# MSP430_REV1_5_21_19_NEW1.net
KiCad netlist of a schematic drawn in EAGLE
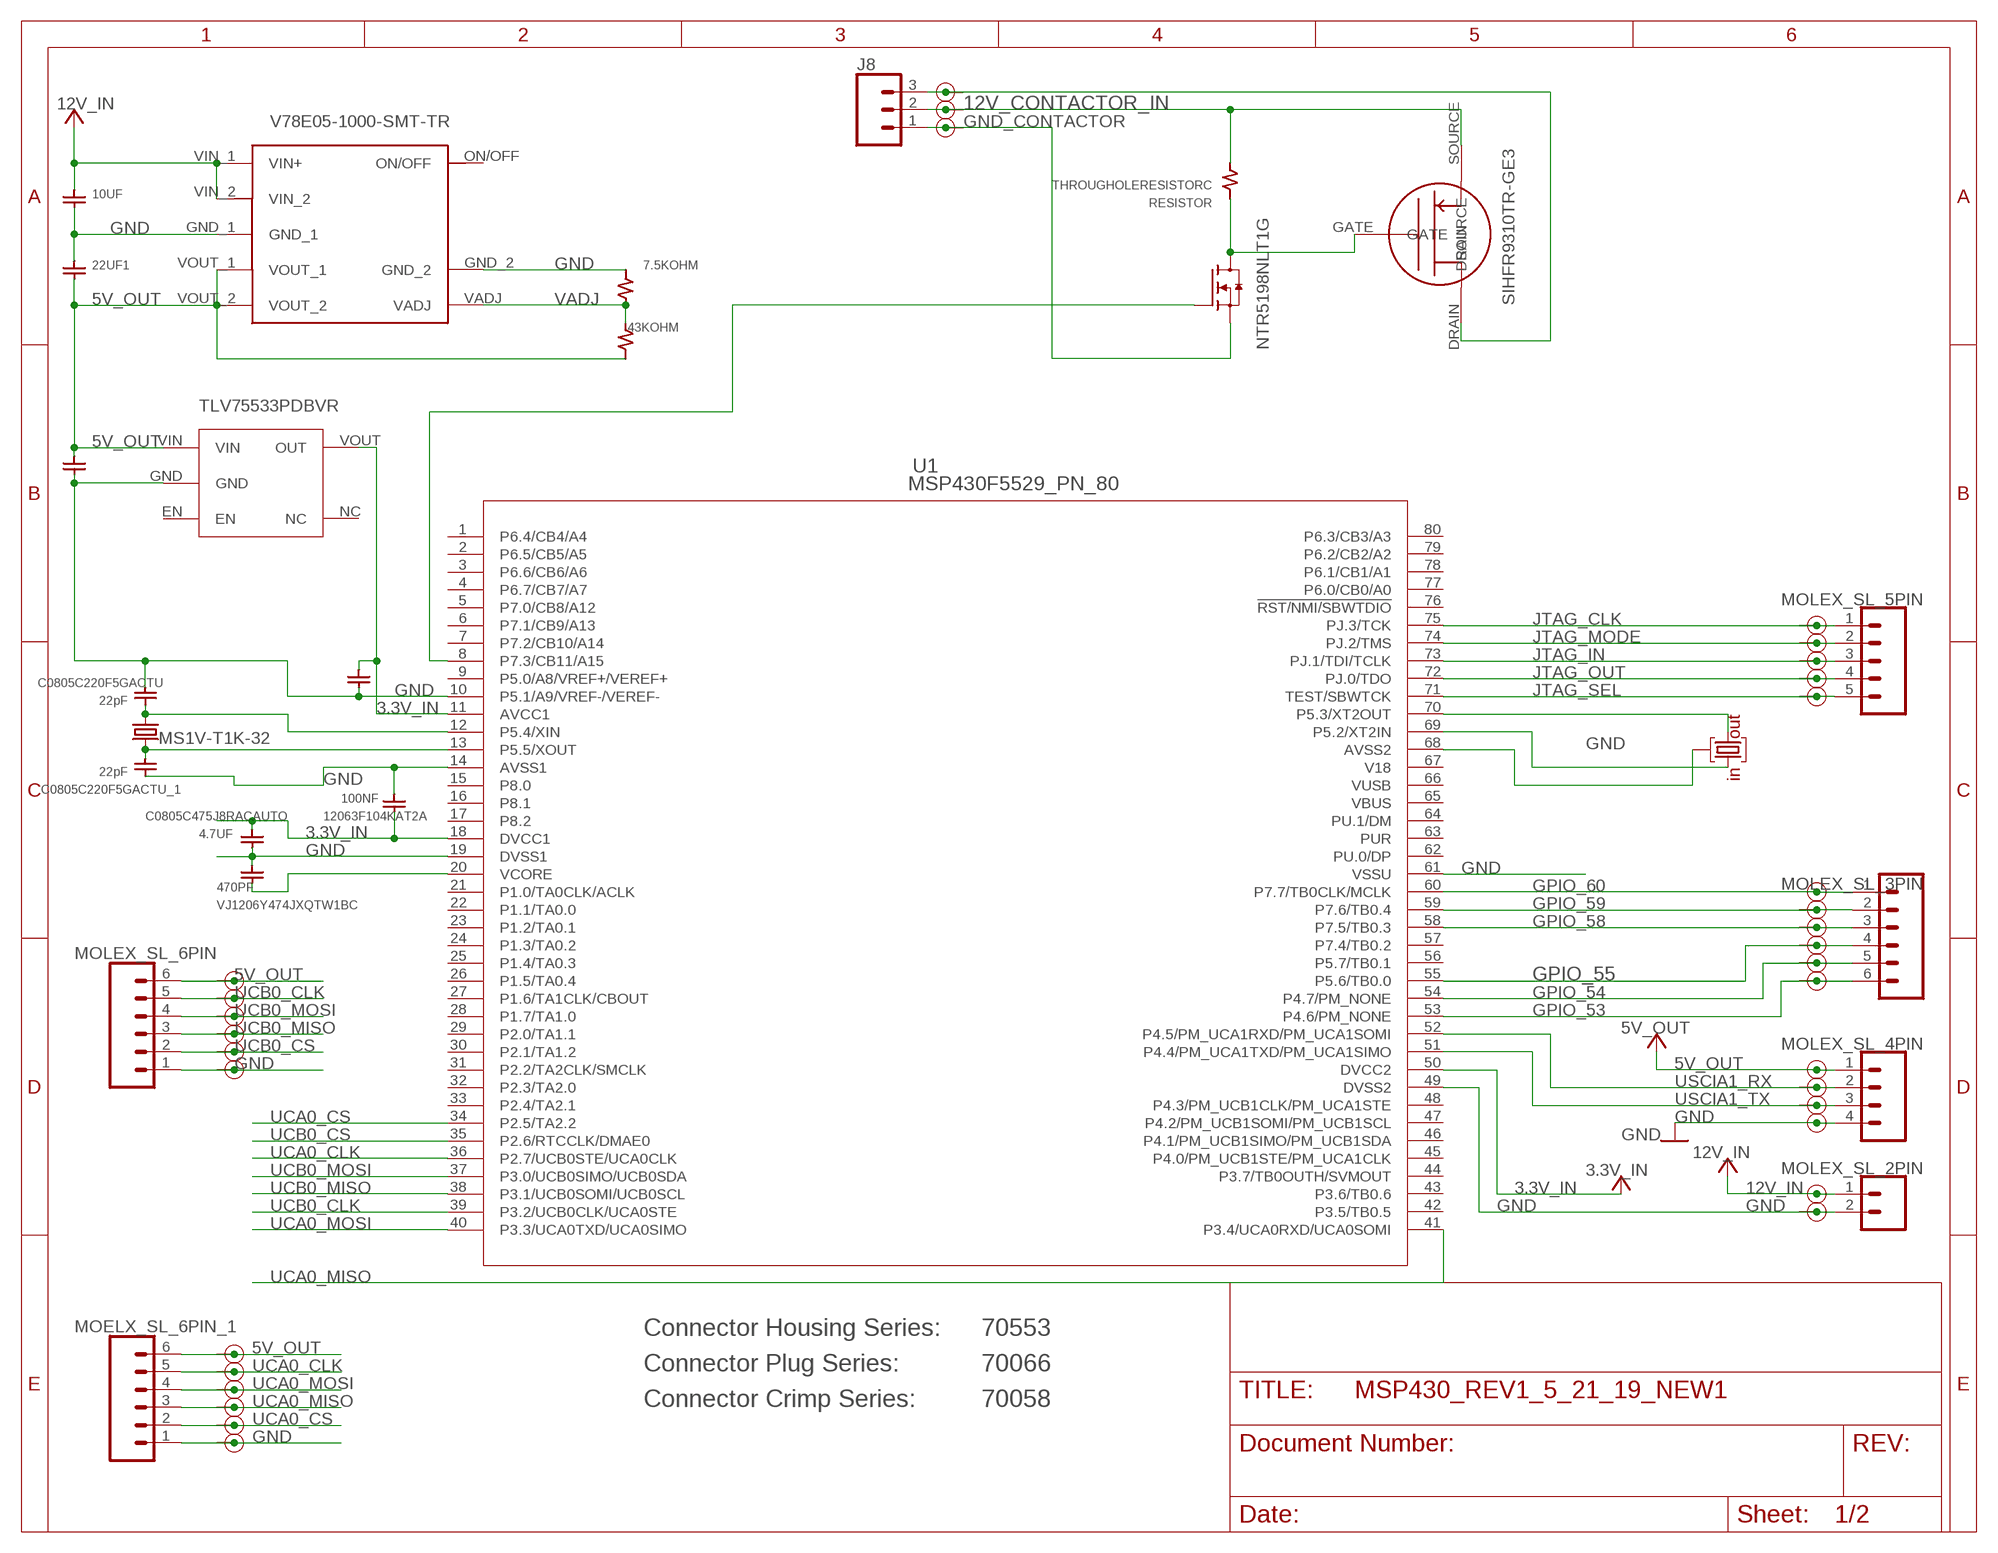
[diagram p0: schematic, sheet 1]
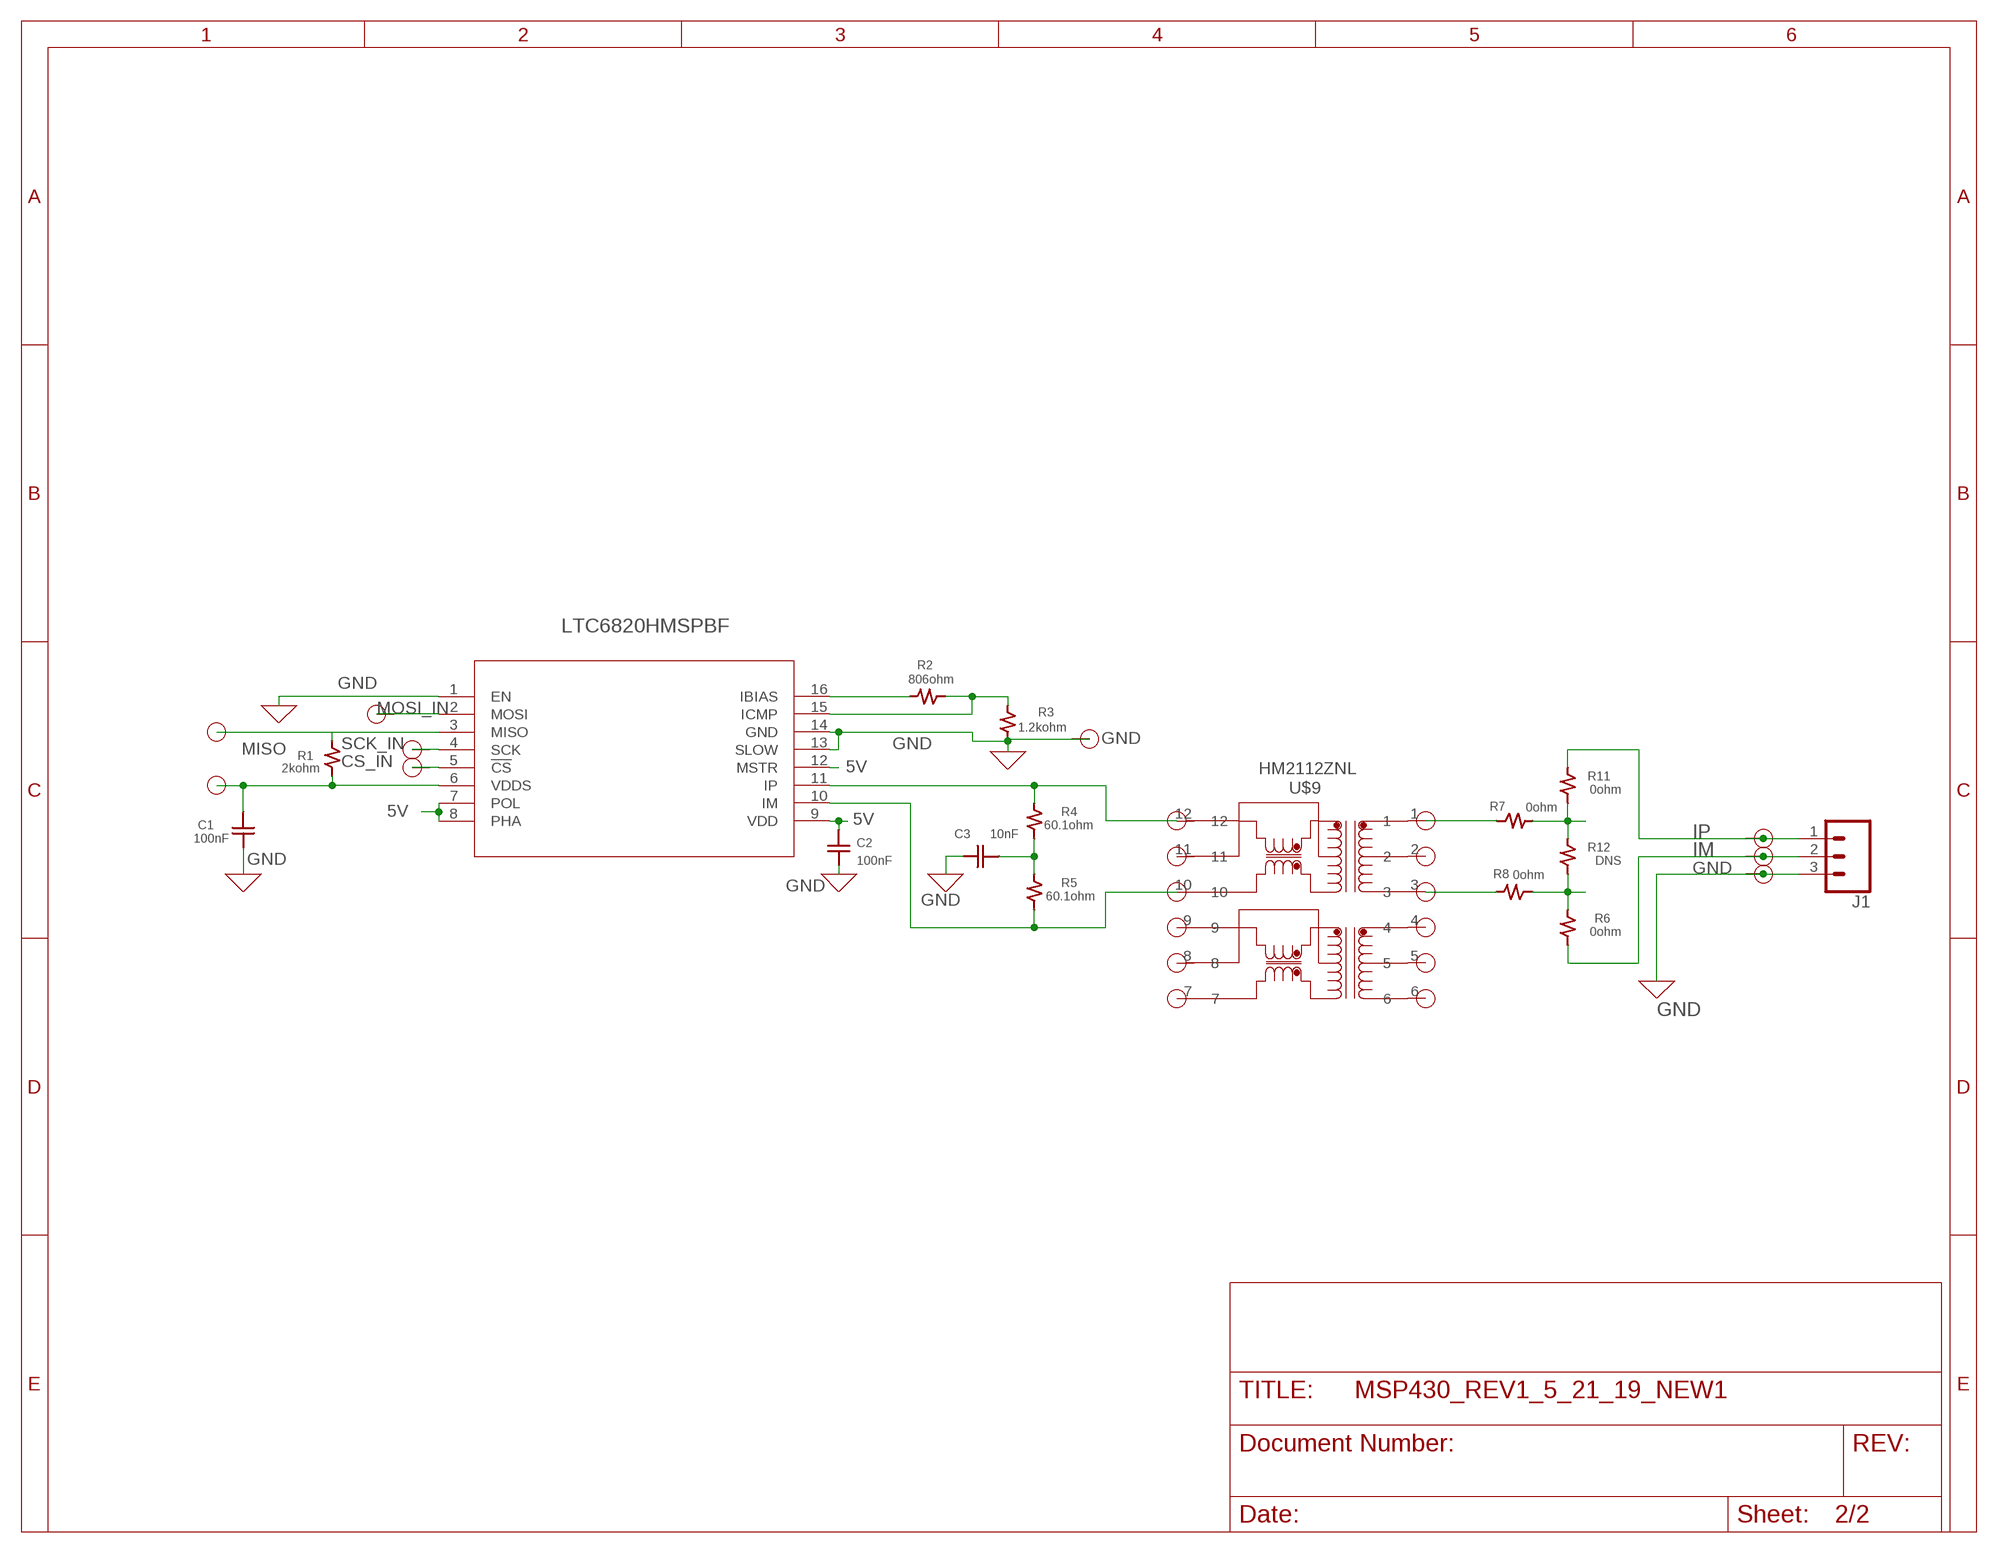
[diagram p1: schematic, sheet 2]

(export (version "E")
  (design (tool "Eeschema 10.0.6"))
  (components
    (comp (ref "C1")
      (value "100nF")
      (footprint "eagle-import:0805_CAPACITOR")
      (fields (field (name "MPN") "MC0805B104K160CT"))
      (libsource (lib "eagle-import") (part "0805_CAPACITOR"))
    )
    (comp (ref "C2")
      (value "100nF")
      (footprint "eagle-import:0805_CAPACITOR")
      (fields (field (name "MPN") "MC0805B104K160CT"))
      (libsource (lib "eagle-import") (part "0805_CAPACITOR"))
    )
    (comp (ref "C3")
      (value "10nF")
      (footprint "eagle-import:0805_CAPACITOR")
      (fields (field (name "MPN") "MC0805B104K160CT"))
      (libsource (lib "eagle-import") (part "0805_CAPACITOR"))
    )
    (comp (ref "CS")
      (value "HEADER_PIN_2.15/1.0")
      (footprint "eagle-import:2,15_1,0")
      (libsource (lib "eagle-import") (part "HEADER_PIN_2.15/1.0"))
    )
    (comp (ref "GND")
      (value "HEADER_PIN_2.15/1.0")
      (footprint "eagle-import:2,15_1,0")
      (libsource (lib "eagle-import") (part "HEADER_PIN_2.15/1.0"))
    )
    (comp (ref "J1")
      (value "CONN_03")
      (footprint "eagle-import:1X03")
      (libsource (lib "eagle-import") (part "CONN_03"))
    )
    (comp (ref "MISO")
      (value "HEADER_PIN_2.15/1.0")
      (footprint "eagle-import:2,15_1,0")
      (libsource (lib "eagle-import") (part "HEADER_PIN_2.15/1.0"))
    )
    (comp (ref "MOSI")
      (value "HEADER_PIN_2.15/1.0")
      (footprint "eagle-import:2,15_1,0")
      (libsource (lib "eagle-import") (part "HEADER_PIN_2.15/1.0"))
    )
    (comp (ref "R1")
      (value "2kohm")
      (footprint "eagle-import:0805_RESISTOR")
      (fields (field (name "MPN") "ERJ-6ENF2001V"))
      (libsource (lib "eagle-import") (part "0805_RESISTOR"))
    )
    (comp (ref "R2")
      (value "806ohm")
      (footprint "eagle-import:0805_RESISTOR")
      (fields (field (name "MF") "VISHAY/DALE") (field (name "MPN") "CRCW0805806RFKEA"))
      (libsource (lib "eagle-import") (part "0805_RESISTOR"))
    )
    (comp (ref "R3")
      (value "1.2kohm")
      (footprint "eagle-import:0805_RESISTOR")
      (fields (field (name "MPN") "MC0805S8F1201T5E"))
      (libsource (lib "eagle-import") (part "0805_RESISTOR"))
    )
    (comp (ref "R4")
      (value "60.1ohm")
      (footprint "eagle-import:0805_RESISTOR")
      (fields (field (name "MF") "BOURNS, INC.") (field (name "MPN") "CR0805-FX-1200GLF"))
      (libsource (lib "eagle-import") (part "0805_RESISTOR"))
    )
    (comp (ref "R5")
      (value "60.1ohm")
      (footprint "eagle-import:0805_RESISTOR")
      (fields (field (name "MF") "BOURNS, INC.") (field (name "MPN") "CR0805-FX-1200GLF"))
      (libsource (lib "eagle-import") (part "0805_RESISTOR"))
    )
    (comp (ref "R6")
      (value "0ohm")
      (footprint "eagle-import:0805_RESISTOR")
      (fields (field (name "MF") "BOURNS, INC.") (field (name "MPN") "CR0805-FX-1200GLF"))
      (libsource (lib "eagle-import") (part "0805_RESISTOR"))
    )
    (comp (ref "R7")
      (value "0ohm")
      (footprint "eagle-import:0805_RESISTOR")
      (fields (field (name "MF") "BOURNS, INC.") (field (name "MPN") "CR0805-FX-1200GLF"))
      (libsource (lib "eagle-import") (part "0805_RESISTOR"))
    )
    (comp (ref "R8")
      (value "0ohm")
      (footprint "eagle-import:0805_RESISTOR")
      (fields (field (name "MF") "BOURNS, INC.") (field (name "MPN") "CR0805-FX-1200GLF"))
      (libsource (lib "eagle-import") (part "0805_RESISTOR"))
    )
    (comp (ref "R11")
      (value "0ohm")
      (footprint "eagle-import:0805_RESISTOR")
      (fields (field (name "MF") "BOURNS, INC.") (field (name "MPN") "CR0805-FX-1200GLF"))
      (libsource (lib "eagle-import") (part "0805_RESISTOR"))
    )
    (comp (ref "R12")
      (value "DNS")
      (footprint "eagle-import:0805_RESISTOR")
      (fields (field (name "MF") "BOURNS, INC.") (field (name "MPN") "CR0805-FX-1200GLF"))
      (libsource (lib "eagle-import") (part "0805_RESISTOR"))
    )
    (comp (ref "SCK")
      (value "HEADER_PIN_2.15/1.0")
      (footprint "eagle-import:2,15_1,0")
      (libsource (lib "eagle-import") (part "HEADER_PIN_2.15/1.0"))
    )
    (comp (ref "U$9")
      (value "HM2112ZNL")
      (footprint "eagle-import:HM2112ZNL_12SMT")
      (libsource (lib "eagle-import") (part "HM2112ZNL"))
    )
    (comp (ref "U$42")
      (value "HEADER_PIN_2.15/1.0")
      (footprint "eagle-import:2,15_1,0")
      (libsource (lib "eagle-import") (part "HEADER_PIN_2.15/1.0"))
    )
    (comp (ref "U$43")
      (value "HEADER_PIN_2.15/1.0")
      (footprint "eagle-import:2,15_1,0")
      (libsource (lib "eagle-import") (part "HEADER_PIN_2.15/1.0"))
    )
    (comp (ref "U$44")
      (value "HEADER_PIN_2.15/1.0")
      (footprint "eagle-import:2,15_1,0")
      (libsource (lib "eagle-import") (part "HEADER_PIN_2.15/1.0"))
    )
    (comp (ref "U2")
      (value "LTC6820HMSPBF")
      (footprint "eagle-import:MSOP-16_MS")
      (fields (field (name "MANUFACTURER_PART_NUMBER") "LTC6820HMS#PBF"))
      (libsource (lib "eagle-import") (part "LTC6820HMSPBF"))
    )
    (comp (ref "VDDS")
      (value "HEADER_PIN_2.15/1.0")
      (footprint "eagle-import:2,15_1,0")
      (libsource (lib "eagle-import") (part "HEADER_PIN_2.15/1.0"))
    )
    (comp (ref "4.7UF")
      (value "C0805C475J8RACAUTO")
      (footprint "eagle-import:C0805C475J8RACAUTO")
      (libsource (lib "eagle-import") (part "C0805C475J8RACAUTO"))
    )
    (comp (ref "7.5KOHM")
      (value "RC2512FK-077K5L")
      (footprint "eagle-import:RC2512FK-077K5L")
      (libsource (lib "eagle-import") (part "RC2512FK-077K5L"))
    )
    (comp (ref "10UF")
      (value "GRT31CR61H106KE01L")
      (footprint "eagle-import:GRT31CR61H106KE01L")
      (libsource (lib "eagle-import") (part "GRT31CR61H106KE01L"))
    )
    (comp (ref "22UF1")
      (value "GRT31CC81C226KE01L")
      (footprint "eagle-import:GRT31CC81C226KE01L")
      (libsource (lib "eagle-import") (part "GRT31CC81C226KE01L"))
    )
    (comp (ref "43KOHM")
      (value "CRCW121043K0FKEAHP")
      (footprint "eagle-import:CRCW121043K0FKEAHP")
      (libsource (lib "eagle-import") (part "CRCW121043K0FKEAHP"))
    )
    (comp (ref "100NF")
      (value "12063F104KAT2A")
      (footprint "eagle-import:12063F104KAT2A")
      (libsource (lib "eagle-import") (part "12063F104KAT2A"))
    )
    (comp (ref "470PF")
      (value "VJ1206Y474JXQTW1BC")
      (footprint "eagle-import:VJ1206Y474JXQTW1BC")
      (libsource (lib "eagle-import") (part "VJ1206Y474JXQTW1BC"))
    )
    (comp (ref "C0805C220F5GACTU")
      (value "22pF")
      (footprint "eagle-import:C0805C220F5GACTU")
      (libsource (lib "eagle-import") (part "C0805C220F5GACTUC0805C220F5GACTU"))
    )
    (comp (ref "C0805C220F5GACTU_1")
      (value "22pF")
      (footprint "eagle-import:C0805C220F5GACTU")
      (libsource (lib "eagle-import") (part "C0805C220F5GACTUC0805C220F5GACTU"))
    )
    (comp (ref "J8")
      (value "CONN_03")
      (footprint "eagle-import:1X03")
      (libsource (lib "eagle-import") (part "CONN_03"))
    )
    (comp (ref "MOELX_SL_6PIN_1")
      (value "CONN_06SILK_FEMALE_PTH")
      (footprint "eagle-import:1X06")
      (libsource (lib "eagle-import") (part "CONN_06SILK_FEMALE_PTH"))
    )
    (comp (ref "MOLEX_SL_2PIN")
      (value "CONN_02")
      (footprint "eagle-import:1X02")
      (libsource (lib "eagle-import") (part "CONN_02"))
    )
    (comp (ref "MOLEX_SL_3PIN")
      (value "CONN_06SILK_FEMALE_PTH")
      (footprint "eagle-import:1X06")
      (libsource (lib "eagle-import") (part "CONN_06SILK_FEMALE_PTH"))
    )
    (comp (ref "MOLEX_SL_4PIN")
      (value "CONN_04")
      (footprint "eagle-import:1X04")
      (libsource (lib "eagle-import") (part "CONN_04"))
    )
    (comp (ref "MOLEX_SL_5PIN")
      (value "CONN_05")
      (footprint "eagle-import:1X05")
      (libsource (lib "eagle-import") (part "CONN_05"))
    )
    (comp (ref "MOLEX_SL_6PIN")
      (value "CONN_06SILK_FEMALE_PTH")
      (footprint "eagle-import:1X06")
      (libsource (lib "eagle-import") (part "CONN_06SILK_FEMALE_PTH"))
    )
    (comp (ref "RESISTOR")
      (value "THROUGHOLERESISTORC")
      (footprint "eagle-import:THROUGHHOLERESISTOR")
      (libsource (lib "eagle-import") (part "THROUGHOLERESISTORCMF6023K000DHR6"))
    )
    (comp (ref "U$1")
      (value "MS1V-T1K-32")
      (footprint "eagle-import:MS1V-T1K")
      (libsource (lib "eagle-import") (part "MS1V-T1K-32"))
    )
    (comp (ref "U$2")
      (value "CSTCR4M00G53U-R0")
      (footprint "eagle-import:CSTCR4M00G53U-R0")
      (libsource (lib "eagle-import") (part "CSTCR4M00G53U-R0"))
    )
    (comp (ref "U$3")
      (value "V78E05-SMT-TR")
      (footprint "eagle-import:V78E05-1000-SMT-TR")
      (libsource (lib "eagle-import") (part "V78E05-SMT-TR"))
    )
    (comp (ref "U$4")
      (value "NTR5198NLT1G")
      (footprint "eagle-import:NTR5198NLT1G")
      (libsource (lib "eagle-import") (part "NTR5198NLT1G"))
    )
    (comp (ref "U$5")
      (value "PMOS")
      (footprint "eagle-import:SIHFR9310TR-GE3")
      (libsource (lib "eagle-import") (part "PMOS"))
    )
    (comp (ref "U$6")
      (value "TLV75533PDBVR")
      (footprint "eagle-import:TLV75533PDBVR")
      (libsource (lib "eagle-import") (part "TLV75533PDBVR"))
    )
    (comp (ref "U$7")
      (value "C0805C105J4RECTU")
      (footprint "eagle-import:C0805C105J4RECTU")
      (libsource (lib "eagle-import") (part "C0805C105J4RECTU"))
    )
    (comp (ref "U$8")
      (value "C0805C105J4RECTU")
      (footprint "eagle-import:C0805C105J4RECTU")
      (libsource (lib "eagle-import") (part "C0805C105J4RECTU"))
    )
    (comp (ref "U$10")
      (value "HEADER_PIN_2.15/1.0")
      (footprint "eagle-import:2,15_1,0")
      (libsource (lib "eagle-import") (part "HEADER_PIN_2.15/1.0"))
    )
    (comp (ref "U$11")
      (value "HEADER_PIN_2.15/1.0")
      (footprint "eagle-import:2,15_1,0")
      (libsource (lib "eagle-import") (part "HEADER_PIN_2.15/1.0"))
    )
    (comp (ref "U$12")
      (value "HEADER_PIN_2.15/1.0")
      (footprint "eagle-import:2,15_1,0")
      (libsource (lib "eagle-import") (part "HEADER_PIN_2.15/1.0"))
    )
    (comp (ref "U$13")
      (value "HEADER_PIN_2.15/1.0")
      (footprint "eagle-import:2,15_1,0")
      (libsource (lib "eagle-import") (part "HEADER_PIN_2.15/1.0"))
    )
    (comp (ref "U$14")
      (value "HEADER_PIN_2.15/1.0")
      (footprint "eagle-import:2,15_1,0")
      (libsource (lib "eagle-import") (part "HEADER_PIN_2.15/1.0"))
    )
    (comp (ref "U$15")
      (value "HEADER_PIN_2.15/1.0")
      (footprint "eagle-import:2,15_1,0")
      (libsource (lib "eagle-import") (part "HEADER_PIN_2.15/1.0"))
    )
    (comp (ref "U$16")
      (value "HEADER_PIN_2.15/1.0")
      (footprint "eagle-import:2,15_1,0")
      (libsource (lib "eagle-import") (part "HEADER_PIN_2.15/1.0"))
    )
    (comp (ref "U$17")
      (value "HEADER_PIN_2.15/1.0")
      (footprint "eagle-import:2,15_1,0")
      (libsource (lib "eagle-import") (part "HEADER_PIN_2.15/1.0"))
    )
    (comp (ref "U$18")
      (value "HEADER_PIN_2.15/1.0")
      (footprint "eagle-import:2,15_1,0")
      (libsource (lib "eagle-import") (part "HEADER_PIN_2.15/1.0"))
    )
    (comp (ref "U$19")
      (value "HEADER_PIN_2.15/1.0")
      (footprint "eagle-import:2,15_1,0")
      (libsource (lib "eagle-import") (part "HEADER_PIN_2.15/1.0"))
    )
    (comp (ref "U$20")
      (value "HEADER_PIN_2.15/1.0")
      (footprint "eagle-import:2,15_1,0")
      (libsource (lib "eagle-import") (part "HEADER_PIN_2.15/1.0"))
    )
    (comp (ref "U$21")
      (value "HEADER_PIN_2.15/1.0")
      (footprint "eagle-import:2,15_1,0")
      (libsource (lib "eagle-import") (part "HEADER_PIN_2.15/1.0"))
    )
    (comp (ref "U$22")
      (value "HEADER_PIN_2.15/1.0")
      (footprint "eagle-import:2,15_1,0")
      (libsource (lib "eagle-import") (part "HEADER_PIN_2.15/1.0"))
    )
    (comp (ref "U$23")
      (value "HEADER_PIN_2.15/1.0")
      (footprint "eagle-import:2,15_1,0")
      (libsource (lib "eagle-import") (part "HEADER_PIN_2.15/1.0"))
    )
    (comp (ref "U$24")
      (value "HEADER_PIN_2.15/1.0")
      (footprint "eagle-import:2,15_1,0")
      (libsource (lib "eagle-import") (part "HEADER_PIN_2.15/1.0"))
    )
    (comp (ref "U$25")
      (value "HEADER_PIN_2.15/1.0")
      (footprint "eagle-import:2,15_1,0")
      (libsource (lib "eagle-import") (part "HEADER_PIN_2.15/1.0"))
    )
    (comp (ref "U$26")
      (value "HEADER_PIN_2.15/1.0")
      (footprint "eagle-import:2,15_1,0")
      (libsource (lib "eagle-import") (part "HEADER_PIN_2.15/1.0"))
    )
    (comp (ref "U$27")
      (value "HEADER_PIN_2.15/1.0")
      (footprint "eagle-import:2,15_1,0")
      (libsource (lib "eagle-import") (part "HEADER_PIN_2.15/1.0"))
    )
    (comp (ref "U$28")
      (value "HEADER_PIN_2.15/1.0")
      (footprint "eagle-import:2,15_1,0")
      (libsource (lib "eagle-import") (part "HEADER_PIN_2.15/1.0"))
    )
    (comp (ref "U$29")
      (value "HEADER_PIN_2.15/1.0")
      (footprint "eagle-import:2,15_1,0")
      (libsource (lib "eagle-import") (part "HEADER_PIN_2.15/1.0"))
    )
    (comp (ref "U$30")
      (value "HEADER_PIN_2.15/1.0")
      (footprint "eagle-import:2,15_1,0")
      (libsource (lib "eagle-import") (part "HEADER_PIN_2.15/1.0"))
    )
    (comp (ref "U$31")
      (value "HEADER_PIN_2.15/1.0")
      (footprint "eagle-import:2,15_1,0")
      (libsource (lib "eagle-import") (part "HEADER_PIN_2.15/1.0"))
    )
    (comp (ref "U$32")
      (value "HEADER_PIN_2.15/1.0")
      (footprint "eagle-import:2,15_1,0")
      (libsource (lib "eagle-import") (part "HEADER_PIN_2.15/1.0"))
    )
    (comp (ref "U$33")
      (value "HEADER_PIN_2.15/1.0")
      (footprint "eagle-import:2,15_1,0")
      (libsource (lib "eagle-import") (part "HEADER_PIN_2.15/1.0"))
    )
    (comp (ref "U$34")
      (value "HEADER_PIN_2.15/1.0")
      (footprint "eagle-import:2,15_1,0")
      (libsource (lib "eagle-import") (part "HEADER_PIN_2.15/1.0"))
    )
    (comp (ref "U$35")
      (value "HEADER_PIN_2.15/1.0")
      (footprint "eagle-import:2,15_1,0")
      (libsource (lib "eagle-import") (part "HEADER_PIN_2.15/1.0"))
    )
    (comp (ref "U$36")
      (value "HEADER_PIN_2.15/1.0")
      (footprint "eagle-import:2,15_1,0")
      (libsource (lib "eagle-import") (part "HEADER_PIN_2.15/1.0"))
    )
    (comp (ref "U$37")
      (value "HEADER_PIN_2.15/1.0")
      (footprint "eagle-import:2,15_1,0")
      (libsource (lib "eagle-import") (part "HEADER_PIN_2.15/1.0"))
    )
    (comp (ref "U$38")
      (value "HEADER_PIN_2.15/1.0")
      (footprint "eagle-import:2,15_1,0")
      (libsource (lib "eagle-import") (part "HEADER_PIN_2.15/1.0"))
    )
    (comp (ref "U$39")
      (value "HEADER_PIN_2.15/1.0")
      (footprint "eagle-import:2,15_1,0")
      (libsource (lib "eagle-import") (part "HEADER_PIN_2.15/1.0"))
    )
    (comp (ref "U$40")
      (value "HEADER_PIN_2.15/1.0")
      (footprint "eagle-import:2,15_1,0")
      (libsource (lib "eagle-import") (part "HEADER_PIN_2.15/1.0"))
    )
    (comp (ref "U$41")
      (value "HEADER_PIN_2.15/1.0")
      (footprint "eagle-import:2,15_1,0")
      (libsource (lib "eagle-import") (part "HEADER_PIN_2.15/1.0"))
    )
    (comp (ref "U1")
      (value "MSP430F5529_PN_80")
      (footprint "eagle-import:PN80")
      (libsource (lib "eagle-import") (part "MSP430F5529_PN_80"))
    )
  )
  (nets
    (net (code "1") (name "3.3V_IN") (class "Default")
      (node (ref "100NF") (pin "1") (pinfunction "P$1_1") (pintype "bidirectional"))
      (node (ref "4.7UF") (pin "2") (pinfunction "P$2_2") (pintype "bidirectional"))
      (node (ref "U$6") (pin "VOUT") (pinfunction "OUT_VOUT") (pintype "bidirectional"))
      (node (ref "U$8") (pin "2") (pinfunction "P$2_2") (pintype "bidirectional"))
      (node (ref "U1") (pin "11") (pinfunction "AVCC1_11") (pintype "power_in"))
      (node (ref "U1") (pin "18") (pinfunction "DVCC1_18") (pintype "power_in"))
      (node (ref "U1") (pin "50") (pinfunction "DVCC2_50") (pintype "power_in"))
    )
    (net (code "2") (name "5V") (class "Default")
      (node (ref "C1") (pin "P$2") (pinfunction "P$2_P$2") (pintype "bidirectional"))
      (node (ref "C2") (pin "P$2") (pinfunction "P$2_P$2") (pintype "bidirectional"))
      (node (ref "R1") (pin "P$2") (pinfunction "P$2_P$2") (pintype "bidirectional"))
      (node (ref "U2") (pin "12") (pinfunction "MSTR_12") (pintype "input"))
      (node (ref "U2") (pin "6") (pinfunction "VDDS_6") (pintype "power_in"))
      (node (ref "U2") (pin "7") (pinfunction "POL_7") (pintype "input"))
      (node (ref "U2") (pin "8") (pinfunction "PHA_8") (pintype "input"))
      (node (ref "U2") (pin "9") (pinfunction "VDD_9") (pintype "power_in"))
      (node (ref "VDDS") (pin "1") (pinfunction "P$1_1") (pintype "bidirectional"))
    )
    (net (code "3") (name "5V_OUT") (class "Default")
      (node (ref "22UF1") (pin "1") (pinfunction "P$1_1") (pintype "bidirectional"))
      (node (ref "43KOHM") (pin "2") (pinfunction "P$2_2") (pintype "bidirectional"))
      (node (ref "MOELX_SL_6PIN_1") (pin "6") (pinfunction "6_6") (pintype "passive"))
      (node (ref "MOLEX_SL_4PIN") (pin "1") (pinfunction "1_1") (pintype "passive"))
      (node (ref "MOLEX_SL_6PIN") (pin "6") (pinfunction "6_6") (pintype "passive"))
      (node (ref "U$11") (pin "1") (pinfunction "P$1_1") (pintype "bidirectional"))
      (node (ref "U$17") (pin "1") (pinfunction "P$1_1") (pintype "bidirectional"))
      (node (ref "U$27") (pin "1") (pinfunction "P$1_1") (pintype "bidirectional"))
      (node (ref "U$3") (pin "VOUT_1") (pinfunction "VOUT_1_VOUT_1") (pintype "output"))
      (node (ref "U$3") (pin "VOUT_2") (pinfunction "VOUT_2_VOUT_2") (pintype "output"))
      (node (ref "U$6") (pin "VIN") (pinfunction "VIN_VIN") (pintype "bidirectional"))
      (node (ref "U$7") (pin "2") (pinfunction "P$2_2") (pintype "bidirectional"))
    )
    (net (code "4") (name "12V_CONTACTOR_IN") (class "Default")
      (node (ref "J8") (pin "2") (pinfunction "2_2") (pintype "passive"))
      (node (ref "RESISTOR") (pin "1") (pinfunction "P$1_1") (pintype "bidirectional"))
      (node (ref "U$40") (pin "1") (pinfunction "P$1_1") (pintype "bidirectional"))
      (node (ref "U$5") (pin "SOURCE") (pinfunction "SOURCE_SOURCE") (pintype "bidirectional"))
    )
    (net (code "5") (name "12V_IN") (class "Default")
      (node (ref "10UF") (pin "2") (pinfunction "P$2_2") (pintype "bidirectional"))
      (node (ref "MOLEX_SL_2PIN") (pin "1") (pinfunction "1_1") (pintype "passive"))
      (node (ref "U$23") (pin "1") (pinfunction "P$1_1") (pintype "bidirectional"))
      (node (ref "U$3") (pin "VIN_1") (pinfunction "VIN+_VIN_1") (pintype "input"))
      (node (ref "U$3") (pin "VIN_2") (pinfunction "VIN_2_VIN_2") (pintype "input"))
    )
    (net (code "6") (name "CS_IN") (class "Default")
      (node (ref "CS") (pin "1") (pinfunction "P$1_1") (pintype "bidirectional"))
      (node (ref "U2") (pin "5") (pinfunction "~{CS}_5") (pintype "bidirectional"))
    )
    (net (code "7") (name "GND") (class "Default")
      (node (ref "100NF") (pin "2") (pinfunction "P$2_2") (pintype "bidirectional"))
      (node (ref "10UF") (pin "1") (pinfunction "P$1_1") (pintype "bidirectional"))
      (node (ref "22UF1") (pin "2") (pinfunction "P$2_2") (pintype "bidirectional"))
      (node (ref "4.7UF") (pin "1") (pinfunction "P$1_1") (pintype "bidirectional"))
      (node (ref "470PF") (pin "2") (pinfunction "P$2_2") (pintype "bidirectional"))
      (node (ref "7.5KOHM") (pin "2") (pinfunction "P$2_2") (pintype "bidirectional"))
      (node (ref "C0805C220F5GACTU") (pin "1") (pinfunction "P$1_1") (pintype "bidirectional"))
      (node (ref "C0805C220F5GACTU_1") (pin "2") (pinfunction "P$2_2") (pintype "bidirectional"))
      (node (ref "C1") (pin "P$1") (pinfunction "P$1_P$1") (pintype "bidirectional"))
      (node (ref "C2") (pin "P$1") (pinfunction "P$1_P$1") (pintype "bidirectional"))
      (node (ref "C3") (pin "P$1") (pinfunction "P$1_P$1") (pintype "bidirectional"))
      (node (ref "GND") (pin "1") (pinfunction "P$1_1") (pintype "bidirectional"))
      (node (ref "J1") (pin "3") (pinfunction "3_3") (pintype "passive"))
      (node (ref "MOELX_SL_6PIN_1") (pin "1") (pinfunction "1_1") (pintype "passive"))
      (node (ref "MOLEX_SL_2PIN") (pin "2") (pinfunction "2_2") (pintype "passive"))
      (node (ref "MOLEX_SL_4PIN") (pin "4") (pinfunction "4_4") (pintype "passive"))
      (node (ref "MOLEX_SL_6PIN") (pin "1") (pinfunction "1_1") (pintype "passive"))
      (node (ref "R3") (pin "P$2") (pinfunction "P$2_P$2") (pintype "bidirectional"))
      (node (ref "U$10") (pin "1") (pinfunction "P$1_1") (pintype "bidirectional"))
      (node (ref "U$16") (pin "1") (pinfunction "P$1_1") (pintype "bidirectional"))
      (node (ref "U$2") (pin "GND") (pinfunction "GND_GND") (pintype "passive"))
      (node (ref "U$22") (pin "1") (pinfunction "P$1_1") (pintype "bidirectional"))
      (node (ref "U$24") (pin "1") (pinfunction "P$1_1") (pintype "bidirectional"))
      (node (ref "U$3") (pin "GND_1") (pinfunction "GND_1_GND_1") (pintype "bidirectional"))
      (node (ref "U$3") (pin "GND_2") (pinfunction "GND_2_GND_2") (pintype "bidirectional"))
      (node (ref "U$44") (pin "1") (pinfunction "P$1_1") (pintype "bidirectional"))
      (node (ref "U$6") (pin "GND") (pinfunction "GND_GND") (pintype "bidirectional"))
      (node (ref "U$7") (pin "1") (pinfunction "P$1_1") (pintype "bidirectional"))
      (node (ref "U$8") (pin "1") (pinfunction "P$1_1") (pintype "bidirectional"))
      (node (ref "U1") (pin "10") (pinfunction "P5.1/A9/VREF-/VEREF-_10") (pintype "bidirectional"))
      (node (ref "U1") (pin "14") (pinfunction "AVSS1_14") (pintype "power_in"))
      (node (ref "U1") (pin "19") (pinfunction "DVSS1_19") (pintype "power_in"))
      (node (ref "U1") (pin "49") (pinfunction "DVSS2_49") (pintype "power_in"))
      (node (ref "U1") (pin "61") (pinfunction "VSSU_61") (pintype "power_in"))
      (node (ref "U1") (pin "68") (pinfunction "AVSS2_68") (pintype "power_in"))
      (node (ref "U2") (pin "1") (pinfunction "EN_1") (pintype "input"))
      (node (ref "U2") (pin "13") (pinfunction "SLOW_13") (pintype "input"))
      (node (ref "U2") (pin "14") (pinfunction "GND_14") (pintype "power_in"))
    )
    (net (code "8") (name "GND_CONTACTOR") (class "Default")
      (node (ref "J8") (pin "1") (pinfunction "1_1") (pintype "passive"))
      (node (ref "U$4") (pin "SOURCE") (pinfunction "SOURCE_SOURCE") (pintype "passive"))
      (node (ref "U$41") (pin "1") (pinfunction "P$1_1") (pintype "bidirectional"))
    )
    (net (code "9") (name "GPIO_53") (class "Default")
      (node (ref "MOLEX_SL_3PIN") (pin "6") (pinfunction "6_6") (pintype "passive"))
      (node (ref "U$28") (pin "1") (pinfunction "P$1_1") (pintype "bidirectional"))
      (node (ref "U1") (pin "53") (pinfunction "P4.6/PM_NONE_53") (pintype "bidirectional"))
    )
    (net (code "10") (name "GPIO_54") (class "Default")
      (node (ref "MOLEX_SL_3PIN") (pin "5") (pinfunction "5_5") (pintype "passive"))
      (node (ref "U$29") (pin "1") (pinfunction "P$1_1") (pintype "bidirectional"))
      (node (ref "U1") (pin "54") (pinfunction "P4.7/PM_NONE_54") (pintype "bidirectional"))
    )
    (net (code "11") (name "GPIO_55") (class "Default")
      (node (ref "MOLEX_SL_3PIN") (pin "4") (pinfunction "4_4") (pintype "passive"))
      (node (ref "U$30") (pin "1") (pinfunction "P$1_1") (pintype "bidirectional"))
      (node (ref "U1") (pin "55") (pinfunction "P5.6/TB0.0_55") (pintype "bidirectional"))
    )
    (net (code "12") (name "GPIO_58") (class "Default")
      (node (ref "MOLEX_SL_3PIN") (pin "3") (pinfunction "3_3") (pintype "passive"))
      (node (ref "U$31") (pin "1") (pinfunction "P$1_1") (pintype "bidirectional"))
      (node (ref "U1") (pin "58") (pinfunction "P7.5/TB0.3_58") (pintype "bidirectional"))
    )
    (net (code "13") (name "GPIO_59") (class "Default")
      (node (ref "MOLEX_SL_3PIN") (pin "2") (pinfunction "2_2") (pintype "passive"))
      (node (ref "U$32") (pin "1") (pinfunction "P$1_1") (pintype "bidirectional"))
      (node (ref "U1") (pin "59") (pinfunction "P7.6/TB0.4_59") (pintype "bidirectional"))
    )
    (net (code "14") (name "GPIO_60") (class "Default")
      (node (ref "MOLEX_SL_3PIN") (pin "1") (pinfunction "1_1") (pintype "passive"))
      (node (ref "U$33") (pin "1") (pinfunction "P$1_1") (pintype "bidirectional"))
      (node (ref "U1") (pin "60") (pinfunction "P7.7/TB0CLK/MCLK_60") (pintype "bidirectional"))
    )
    (net (code "15") (name "IM") (class "Default")
      (node (ref "J1") (pin "2") (pinfunction "2_2") (pintype "passive"))
      (node (ref "R5") (pin "P$2") (pinfunction "P$2_P$2") (pintype "bidirectional"))
      (node (ref "R6") (pin "P$2") (pinfunction "P$2_P$2") (pintype "bidirectional"))
      (node (ref "U$43") (pin "1") (pinfunction "P$1_1") (pintype "bidirectional"))
      (node (ref "U$9") (pin "10") (pinfunction "10_10") (pintype "bidirectional"))
      (node (ref "U2") (pin "10") (pinfunction "IM_10") (pintype "bidirectional"))
    )
    (net (code "16") (name "IP") (class "Default")
      (node (ref "J1") (pin "1") (pinfunction "1_1") (pintype "passive"))
      (node (ref "R11") (pin "P$1") (pinfunction "P$1_P$1") (pintype "bidirectional"))
      (node (ref "R4") (pin "P$1") (pinfunction "P$1_P$1") (pintype "bidirectional"))
      (node (ref "U$42") (pin "1") (pinfunction "P$1_1") (pintype "bidirectional"))
      (node (ref "U$9") (pin "12") (pinfunction "12_12") (pintype "bidirectional"))
      (node (ref "U2") (pin "11") (pinfunction "IP_11") (pintype "bidirectional"))
    )
    (net (code "17") (name "JTAG_CLK") (class "Default")
      (node (ref "MOLEX_SL_5PIN") (pin "1") (pinfunction "1_1") (pintype "passive"))
      (node (ref "U$38") (pin "1") (pinfunction "P$1_1") (pintype "bidirectional"))
      (node (ref "U1") (pin "75") (pinfunction "PJ.3/TCK_75") (pintype "bidirectional"))
    )
    (net (code "18") (name "JTAG_IN") (class "Default")
      (node (ref "MOLEX_SL_5PIN") (pin "3") (pinfunction "3_3") (pintype "passive"))
      (node (ref "U$36") (pin "1") (pinfunction "P$1_1") (pintype "bidirectional"))
      (node (ref "U1") (pin "73") (pinfunction "PJ.1/TDI/TCLK_73") (pintype "bidirectional"))
    )
    (net (code "19") (name "JTAG_MODE") (class "Default")
      (node (ref "MOLEX_SL_5PIN") (pin "2") (pinfunction "2_2") (pintype "passive"))
      (node (ref "U$37") (pin "1") (pinfunction "P$1_1") (pintype "bidirectional"))
      (node (ref "U1") (pin "74") (pinfunction "PJ.2/TMS_74") (pintype "bidirectional"))
    )
    (net (code "20") (name "JTAG_OUT") (class "Default")
      (node (ref "MOLEX_SL_5PIN") (pin "4") (pinfunction "4_4") (pintype "passive"))
      (node (ref "U$35") (pin "1") (pinfunction "P$1_1") (pintype "bidirectional"))
      (node (ref "U1") (pin "72") (pinfunction "PJ.0/TDO_72") (pintype "bidirectional"))
    )
    (net (code "21") (name "JTAG_SEL") (class "Default")
      (node (ref "MOLEX_SL_5PIN") (pin "5") (pinfunction "5_5") (pintype "passive"))
      (node (ref "U$34") (pin "1") (pinfunction "P$1_1") (pintype "bidirectional"))
      (node (ref "U1") (pin "71") (pinfunction "TEST/SBWTCK_71") (pintype "bidirectional"))
    )
    (net (code "22") (name "MOSI_IN") (class "Default")
      (node (ref "MOSI") (pin "1") (pinfunction "P$1_1") (pintype "bidirectional"))
      (node (ref "U2") (pin "2") (pinfunction "MOSI_2") (pintype "bidirectional"))
    )
    (net (code "23") (name "Net-(470PF-P$1)") (class "Default")
      (node (ref "470PF") (pin "1") (pinfunction "P$1_1") (pintype "bidirectional"))
      (node (ref "U1") (pin "20") (pinfunction "VCORE_20") (pintype "power_in"))
    )
    (net (code "24") (name "Net-(C3-PadP$2)") (class "Default")
      (node (ref "C3") (pin "P$2") (pinfunction "P$2_P$2") (pintype "bidirectional"))
      (node (ref "R4") (pin "P$2") (pinfunction "P$2_P$2") (pintype "bidirectional"))
      (node (ref "R5") (pin "P$1") (pinfunction "P$1_P$1") (pintype "bidirectional"))
    )
    (net (code "25") (name "Net-(C0805C220F5GACTU-P$2)") (class "Default")
      (node (ref "C0805C220F5GACTU") (pin "2") (pinfunction "P$2_2") (pintype "bidirectional"))
      (node (ref "U$1") (pin "P$2") (pinfunction "1_P$2") (pintype "passive"))
      (node (ref "U1") (pin "12") (pinfunction "P5.4/XIN_12") (pintype "bidirectional"))
    )
    (net (code "26") (name "Net-(C0805C220F5GACTU_1-P$1)") (class "Default")
      (node (ref "C0805C220F5GACTU_1") (pin "1") (pinfunction "P$1_1") (pintype "bidirectional"))
      (node (ref "U$1") (pin "P$3") (pinfunction "2_P$3") (pintype "passive"))
      (node (ref "U1") (pin "13") (pinfunction "P5.5/XOUT_13") (pintype "bidirectional"))
    )
    (net (code "27") (name "Net-(MISO-P$1)") (class "Default")
      (node (ref "MISO") (pin "1") (pinfunction "P$1_1") (pintype "bidirectional"))
      (node (ref "R1") (pin "P$1") (pinfunction "P$1_P$1") (pintype "bidirectional"))
      (node (ref "U2") (pin "3") (pinfunction "MISO_3") (pintype "bidirectional"))
    )
    (net (code "28") (name "Net-(R7-PadP$2)") (class "Default")
      (node (ref "R7") (pin "P$2") (pinfunction "P$2_P$2") (pintype "bidirectional"))
      (node (ref "U$9") (pin "1") (pinfunction "1_1") (pintype "bidirectional"))
    )
    (net (code "29") (name "Net-(R8-PadP$1)") (class "Default")
      (node (ref "R8") (pin "P$1") (pinfunction "P$1_P$1") (pintype "bidirectional"))
      (node (ref "U$9") (pin "3") (pinfunction "3_3") (pintype "bidirectional"))
    )
    (net (code "30") (name "Net-(R11-PadP$2)") (class "Default")
      (node (ref "R11") (pin "P$2") (pinfunction "P$2_P$2") (pintype "bidirectional"))
      (node (ref "R12") (pin "P$1") (pinfunction "P$1_P$1") (pintype "bidirectional"))
      (node (ref "R7") (pin "P$1") (pinfunction "P$1_P$1") (pintype "bidirectional"))
    )
    (net (code "31") (name "Net-(R12-PadP$2)") (class "Default")
      (node (ref "R12") (pin "P$2") (pinfunction "P$2_P$2") (pintype "bidirectional"))
      (node (ref "R6") (pin "P$1") (pinfunction "P$1_P$1") (pintype "bidirectional"))
      (node (ref "R8") (pin "P$2") (pinfunction "P$2_P$2") (pintype "bidirectional"))
    )
    (net (code "32") (name "Net-(RESISTOR-P$2)") (class "Default")
      (node (ref "RESISTOR") (pin "2") (pinfunction "P$2_2") (pintype "bidirectional"))
      (node (ref "U$4") (pin "DRAIN") (pinfunction "DRAIN_DRAIN") (pintype "passive"))
      (node (ref "U$5") (pin "GATE") (pinfunction "GATE_GATE") (pintype "bidirectional"))
    )
    (net (code "33") (name "Net-(U$39-P$1)") (class "Default")
      (node (ref "J8") (pin "3") (pinfunction "3_3") (pintype "passive"))
      (node (ref "U$39") (pin "1") (pinfunction "P$1_1") (pintype "bidirectional"))
      (node (ref "U$5") (pin "DRAIN") (pinfunction "DRAIN_DRAIN") (pintype "bidirectional"))
    )
    (net (code "34") (name "Net-(U1-P5.2{slash}XT2IN)") (class "Default")
      (node (ref "U$2") (pin "IN") (pinfunction "IN_IN") (pintype "passive"))
      (node (ref "U1") (pin "69") (pinfunction "P5.2/XT2IN_69") (pintype "bidirectional"))
    )
    (net (code "35") (name "Net-(U1-P5.3{slash}XT2OUT)") (class "Default")
      (node (ref "U$2") (pin "OUT") (pinfunction "OUT_OUT") (pintype "passive"))
      (node (ref "U1") (pin "70") (pinfunction "P5.3/XT2OUT_70") (pintype "bidirectional"))
    )
    (net (code "36") (name "Net-(U1-P7.3{slash}CB11{slash}A15)") (class "Default")
      (node (ref "U$4") (pin "GATE") (pinfunction "GATE_GATE") (pintype "passive"))
      (node (ref "U1") (pin "8") (pinfunction "P7.3/CB11/A15_8") (pintype "bidirectional"))
    )
    (net (code "37") (name "Net-(U2-IBIAS)") (class "Default")
      (node (ref "R2") (pin "P$1") (pinfunction "P$1_P$1") (pintype "bidirectional"))
      (node (ref "U2") (pin "16") (pinfunction "IBIAS_16") (pintype "output"))
    )
    (net (code "38") (name "Net-(U2-ICMP)") (class "Default")
      (node (ref "R2") (pin "P$2") (pinfunction "P$2_P$2") (pintype "bidirectional"))
      (node (ref "R3") (pin "P$1") (pinfunction "P$1_P$1") (pintype "bidirectional"))
      (node (ref "U2") (pin "15") (pinfunction "ICMP_15") (pintype "passive"))
    )
    (net (code "39") (name "SCK_IN") (class "Default")
      (node (ref "SCK") (pin "1") (pinfunction "P$1_1") (pintype "bidirectional"))
      (node (ref "U2") (pin "4") (pinfunction "SCK_4") (pintype "bidirectional"))
    )
    (net (code "40") (name "UCA0_CLK") (class "Default")
      (node (ref "MOELX_SL_6PIN_1") (pin "5") (pinfunction "5_5") (pintype "passive"))
      (node (ref "U$18") (pin "1") (pinfunction "P$1_1") (pintype "bidirectional"))
      (node (ref "U1") (pin "36") (pinfunction "P2.7/UCB0STE/UCA0CLK_36") (pintype "bidirectional"))
    )
    (net (code "41") (name "UCA0_CS") (class "Default")
      (node (ref "MOELX_SL_6PIN_1") (pin "2") (pinfunction "2_2") (pintype "passive"))
      (node (ref "U$21") (pin "1") (pinfunction "P$1_1") (pintype "bidirectional"))
      (node (ref "U1") (pin "34") (pinfunction "P2.5/TA2.2_34") (pintype "bidirectional"))
    )
    (net (code "42") (name "UCA0_MISO") (class "Default")
      (node (ref "MOELX_SL_6PIN_1") (pin "3") (pinfunction "3_3") (pintype "passive"))
      (node (ref "U$20") (pin "1") (pinfunction "P$1_1") (pintype "bidirectional"))
      (node (ref "U1") (pin "41") (pinfunction "P3.4/UCA0RXD/UCA0SOMI_41") (pintype "bidirectional"))
    )
    (net (code "43") (name "UCA0_MOSI") (class "Default")
      (node (ref "MOELX_SL_6PIN_1") (pin "4") (pinfunction "4_4") (pintype "passive"))
      (node (ref "U$19") (pin "1") (pinfunction "P$1_1") (pintype "bidirectional"))
      (node (ref "U1") (pin "40") (pinfunction "P3.3/UCA0TXD/UCA0SIMO_40") (pintype "bidirectional"))
    )
    (net (code "44") (name "UCB0_CLK") (class "Default")
      (node (ref "MOLEX_SL_6PIN") (pin "5") (pinfunction "5_5") (pintype "passive"))
      (node (ref "U$12") (pin "1") (pinfunction "P$1_1") (pintype "bidirectional"))
      (node (ref "U1") (pin "39") (pinfunction "P3.2/UCB0CLK/UCA0STE_39") (pintype "bidirectional"))
    )
    (net (code "45") (name "UCB0_CS") (class "Default")
      (node (ref "MOLEX_SL_6PIN") (pin "2") (pinfunction "2_2") (pintype "passive"))
      (node (ref "U$15") (pin "1") (pinfunction "P$1_1") (pintype "bidirectional"))
      (node (ref "U1") (pin "35") (pinfunction "P2.6/RTCCLK/DMAE0_35") (pintype "bidirectional"))
    )
    (net (code "46") (name "UCB0_MISO") (class "Default")
      (node (ref "MOLEX_SL_6PIN") (pin "3") (pinfunction "3_3") (pintype "passive"))
      (node (ref "U$14") (pin "1") (pinfunction "P$1_1") (pintype "bidirectional"))
      (node (ref "U1") (pin "38") (pinfunction "P3.1/UCB0SOMI/UCB0SCL_38") (pintype "bidirectional"))
    )
    (net (code "47") (name "UCB0_MOSI") (class "Default")
      (node (ref "MOLEX_SL_6PIN") (pin "4") (pinfunction "4_4") (pintype "passive"))
      (node (ref "U$13") (pin "1") (pinfunction "P$1_1") (pintype "bidirectional"))
      (node (ref "U1") (pin "37") (pinfunction "P3.0/UCB0SIMO/UCB0SDA_37") (pintype "bidirectional"))
    )
    (net (code "48") (name "USCIA1_RX") (class "Default")
      (node (ref "MOLEX_SL_4PIN") (pin "2") (pinfunction "2_2") (pintype "passive"))
      (node (ref "U$26") (pin "1") (pinfunction "P$1_1") (pintype "bidirectional"))
      (node (ref "U1") (pin "52") (pinfunction "P4.5/PM_UCA1RXD/PM_UCA1SOMI_52") (pintype "bidirectional"))
    )
    (net (code "49") (name "USCIA1_TX") (class "Default")
      (node (ref "MOLEX_SL_4PIN") (pin "3") (pinfunction "3_3") (pintype "passive"))
      (node (ref "U$25") (pin "1") (pinfunction "P$1_1") (pintype "bidirectional"))
      (node (ref "U1") (pin "51") (pinfunction "P4.4/PM_UCA1TXD/PM_UCA1SIMO_51") (pintype "bidirectional"))
    )
    (net (code "50") (name "V18") (class "Default")
      (node (ref "U1") (pin "67") (pinfunction "V18_67") (pintype "power_in"))
    )
    (net (code "51") (name "VADJ") (class "Default")
      (node (ref "43KOHM") (pin "1") (pinfunction "P$1_1") (pintype "bidirectional"))
      (node (ref "7.5KOHM") (pin "1") (pinfunction "P$1_1") (pintype "bidirectional"))
      (node (ref "U$3") (pin "VADJ") (pinfunction "VADJ_VADJ") (pintype "bidirectional"))
    )
    (net (code "52") (name "VBUS") (class "Default")
      (node (ref "U1") (pin "65") (pinfunction "VBUS_65") (pintype "power_in"))
    )
    (net (code "53") (name "VUSB") (class "Default")
      (node (ref "U1") (pin "66") (pinfunction "VUSB_66") (pintype "power_in"))
    )
    (net (code "54") (name "unconnected-(U$3-PadON{slash}OFF)") (class "Default")
      (node (ref "U$3") (pin "ON/OFF") (pinfunction "ON/OFF_ON/OFF") (pintype "input"))
    )
    (net (code "55") (name "unconnected-(U$6-PadEN)") (class "Default")
      (node (ref "U$6") (pin "EN") (pinfunction "EN_EN") (pintype "bidirectional"))
    )
    (net (code "56") (name "unconnected-(U$6-PadNC)") (class "Default")
      (node (ref "U$6") (pin "NC") (pinfunction "NC_NC") (pintype "bidirectional"))
    )
    (net (code "57") (name "unconnected-(U$9-Pad2)") (class "Default")
      (node (ref "U$9") (pin "2") (pinfunction "2_2") (pintype "bidirectional"))
    )
    (net (code "58") (name "unconnected-(U$9-Pad4)") (class "Default")
      (node (ref "U$9") (pin "4") (pinfunction "4_4") (pintype "bidirectional"))
    )
    (net (code "59") (name "unconnected-(U$9-Pad5)") (class "Default")
      (node (ref "U$9") (pin "5") (pinfunction "5_5") (pintype "bidirectional"))
    )
    (net (code "60") (name "unconnected-(U$9-Pad6)") (class "Default")
      (node (ref "U$9") (pin "6") (pinfunction "6_6") (pintype "bidirectional"))
    )
    (net (code "61") (name "unconnected-(U$9-Pad7)") (class "Default")
      (node (ref "U$9") (pin "7") (pinfunction "7_7") (pintype "bidirectional"))
    )
    (net (code "62") (name "unconnected-(U$9-Pad8)") (class "Default")
      (node (ref "U$9") (pin "8") (pinfunction "8_8") (pintype "bidirectional"))
    )
    (net (code "63") (name "unconnected-(U$9-Pad9)") (class "Default")
      (node (ref "U$9") (pin "9") (pinfunction "9_9") (pintype "bidirectional"))
    )
    (net (code "64") (name "unconnected-(U$9-Pad11)") (class "Default")
      (node (ref "U$9") (pin "11") (pinfunction "11_11") (pintype "bidirectional"))
    )
    (net (code "65") (name "unconnected-(U1-P1.0{slash}TA0CLK{slash}ACLK-Pad21)") (class "Default")
      (node (ref "U1") (pin "21") (pinfunction "P1.0/TA0CLK/ACLK_21") (pintype "bidirectional"))
    )
    (net (code "66") (name "unconnected-(U1-P1.1{slash}TA0.0-Pad22)") (class "Default")
      (node (ref "U1") (pin "22") (pinfunction "P1.1/TA0.0_22") (pintype "bidirectional"))
    )
    (net (code "67") (name "unconnected-(U1-P1.2{slash}TA0.1-Pad23)") (class "Default")
      (node (ref "U1") (pin "23") (pinfunction "P1.2/TA0.1_23") (pintype "bidirectional"))
    )
    (net (code "68") (name "unconnected-(U1-P1.3{slash}TA0.2-Pad24)") (class "Default")
      (node (ref "U1") (pin "24") (pinfunction "P1.3/TA0.2_24") (pintype "bidirectional"))
    )
    (net (code "69") (name "unconnected-(U1-P1.4{slash}TA0.3-Pad25)") (class "Default")
      (node (ref "U1") (pin "25") (pinfunction "P1.4/TA0.3_25") (pintype "bidirectional"))
    )
    (net (code "70") (name "unconnected-(U1-P1.5{slash}TA0.4-Pad26)") (class "Default")
      (node (ref "U1") (pin "26") (pinfunction "P1.5/TA0.4_26") (pintype "bidirectional"))
    )
    (net (code "71") (name "unconnected-(U1-P1.6{slash}TA1CLK{slash}CBOUT-Pad27)") (class "Default")
      (node (ref "U1") (pin "27") (pinfunction "P1.6/TA1CLK/CBOUT_27") (pintype "bidirectional"))
    )
    (net (code "72") (name "unconnected-(U1-P1.7{slash}TA1.0-Pad28)") (class "Default")
      (node (ref "U1") (pin "28") (pinfunction "P1.7/TA1.0_28") (pintype "bidirectional"))
    )
    (net (code "73") (name "unconnected-(U1-P2.0{slash}TA1.1-Pad29)") (class "Default")
      (node (ref "U1") (pin "29") (pinfunction "P2.0/TA1.1_29") (pintype "bidirectional"))
    )
    (net (code "74") (name "unconnected-(U1-P2.1{slash}TA1.2-Pad30)") (class "Default")
      (node (ref "U1") (pin "30") (pinfunction "P2.1/TA1.2_30") (pintype "bidirectional"))
    )
    (net (code "75") (name "unconnected-(U1-P2.2{slash}TA2CLK{slash}SMCLK-Pad31)") (class "Default")
      (node (ref "U1") (pin "31") (pinfunction "P2.2/TA2CLK/SMCLK_31") (pintype "bidirectional"))
    )
    (net (code "76") (name "unconnected-(U1-P2.3{slash}TA2.0-Pad32)") (class "Default")
      (node (ref "U1") (pin "32") (pinfunction "P2.3/TA2.0_32") (pintype "bidirectional"))
    )
    (net (code "77") (name "unconnected-(U1-P2.4{slash}TA2.1-Pad33)") (class "Default")
      (node (ref "U1") (pin "33") (pinfunction "P2.4/TA2.1_33") (pintype "bidirectional"))
    )
    (net (code "78") (name "unconnected-(U1-P3.5{slash}TB0.5-Pad42)") (class "Default")
      (node (ref "U1") (pin "42") (pinfunction "P3.5/TB0.5_42") (pintype "bidirectional"))
    )
    (net (code "79") (name "unconnected-(U1-P3.6{slash}TB0.6-Pad43)") (class "Default")
      (node (ref "U1") (pin "43") (pinfunction "P3.6/TB0.6_43") (pintype "bidirectional"))
    )
    (net (code "80") (name "unconnected-(U1-P3.7{slash}TB0OUTH{slash}SVMOUT-Pad44)") (class "Default")
      (node (ref "U1") (pin "44") (pinfunction "P3.7/TB0OUTH/SVMOUT_44") (pintype "bidirectional"))
    )
    (net (code "81") (name "unconnected-(U1-P4.0{slash}PM_UCB1STE{slash}PM_UCA1CLK-Pad45)") (class "Default")
      (node (ref "U1") (pin "45") (pinfunction "P4.0/PM_UCB1STE/PM_UCA1CLK_45") (pintype "bidirectional"))
    )
    (net (code "82") (name "unconnected-(U1-P4.1{slash}PM_UCB1SIMO{slash}PM_UCB1SDA-Pad46)") (class "Default")
      (node (ref "U1") (pin "46") (pinfunction "P4.1/PM_UCB1SIMO/PM_UCB1SDA_46") (pintype "bidirectional"))
    )
    (net (code "83") (name "unconnected-(U1-P4.2{slash}PM_UCB1SOMI{slash}PM_UCB1SCL-Pad47)") (class "Default")
      (node (ref "U1") (pin "47") (pinfunction "P4.2/PM_UCB1SOMI/PM_UCB1SCL_47") (pintype "bidirectional"))
    )
    (net (code "84") (name "unconnected-(U1-P4.3{slash}PM_UCB1CLK{slash}PM_UCA1STE-Pad48)") (class "Default")
      (node (ref "U1") (pin "48") (pinfunction "P4.3/PM_UCB1CLK/PM_UCA1STE_48") (pintype "bidirectional"))
    )
    (net (code "85") (name "unconnected-(U1-P5.0{slash}A8{slash}VREF+{slash}VEREF+-Pad9)") (class "Default")
      (node (ref "U1") (pin "9") (pinfunction "P5.0/A8/VREF+/VEREF+_9") (pintype "bidirectional"))
    )
    (net (code "86") (name "unconnected-(U1-P5.7{slash}TB0.1-Pad56)") (class "Default")
      (node (ref "U1") (pin "56") (pinfunction "P5.7/TB0.1_56") (pintype "bidirectional"))
    )
    (net (code "87") (name "unconnected-(U1-P6.0{slash}CB0{slash}A0-Pad77)") (class "Default")
      (node (ref "U1") (pin "77") (pinfunction "P6.0/CB0/A0_77") (pintype "bidirectional"))
    )
    (net (code "88") (name "unconnected-(U1-P6.1{slash}CB1{slash}A1-Pad78)") (class "Default")
      (node (ref "U1") (pin "78") (pinfunction "P6.1/CB1/A1_78") (pintype "bidirectional"))
    )
    (net (code "89") (name "unconnected-(U1-P6.2{slash}CB2{slash}A2-Pad79)") (class "Default")
      (node (ref "U1") (pin "79") (pinfunction "P6.2/CB2/A2_79") (pintype "bidirectional"))
    )
    (net (code "90") (name "unconnected-(U1-P6.3{slash}CB3{slash}A3-Pad80)") (class "Default")
      (node (ref "U1") (pin "80") (pinfunction "P6.3/CB3/A3_80") (pintype "bidirectional"))
    )
    (net (code "91") (name "unconnected-(U1-P6.4{slash}CB4{slash}A4-Pad1)") (class "Default")
      (node (ref "U1") (pin "1") (pinfunction "P6.4/CB4/A4_1") (pintype "bidirectional"))
    )
    (net (code "92") (name "unconnected-(U1-P6.5{slash}CB5{slash}A5-Pad2)") (class "Default")
      (node (ref "U1") (pin "2") (pinfunction "P6.5/CB5/A5_2") (pintype "bidirectional"))
    )
    (net (code "93") (name "unconnected-(U1-P6.6{slash}CB6{slash}A6-Pad3)") (class "Default")
      (node (ref "U1") (pin "3") (pinfunction "P6.6/CB6/A6_3") (pintype "bidirectional"))
    )
    (net (code "94") (name "unconnected-(U1-P6.7{slash}CB7{slash}A7-Pad4)") (class "Default")
      (node (ref "U1") (pin "4") (pinfunction "P6.7/CB7/A7_4") (pintype "bidirectional"))
    )
    (net (code "95") (name "unconnected-(U1-P7.0{slash}CB8{slash}A12-Pad5)") (class "Default")
      (node (ref "U1") (pin "5") (pinfunction "P7.0/CB8/A12_5") (pintype "bidirectional"))
    )
    (net (code "96") (name "unconnected-(U1-P7.1{slash}CB9{slash}A13-Pad6)") (class "Default")
      (node (ref "U1") (pin "6") (pinfunction "P7.1/CB9/A13_6") (pintype "bidirectional"))
    )
    (net (code "97") (name "unconnected-(U1-P7.2{slash}CB10{slash}A14-Pad7)") (class "Default")
      (node (ref "U1") (pin "7") (pinfunction "P7.2/CB10/A14_7") (pintype "bidirectional"))
    )
    (net (code "98") (name "unconnected-(U1-P7.4{slash}TB0.2-Pad57)") (class "Default")
      (node (ref "U1") (pin "57") (pinfunction "P7.4/TB0.2_57") (pintype "bidirectional"))
    )
    (net (code "99") (name "unconnected-(U1-P8.0-Pad15)") (class "Default")
      (node (ref "U1") (pin "15") (pinfunction "P8.0_15") (pintype "bidirectional"))
    )
    (net (code "100") (name "unconnected-(U1-P8.1-Pad16)") (class "Default")
      (node (ref "U1") (pin "16") (pinfunction "P8.1_16") (pintype "bidirectional"))
    )
    (net (code "101") (name "unconnected-(U1-P8.2-Pad17)") (class "Default")
      (node (ref "U1") (pin "17") (pinfunction "P8.2_17") (pintype "bidirectional"))
    )
    (net (code "102") (name "unconnected-(U1-PU.0{slash}DP-Pad62)") (class "Default")
      (node (ref "U1") (pin "62") (pinfunction "PU.0/DP_62") (pintype "bidirectional"))
    )
    (net (code "103") (name "unconnected-(U1-PU.1{slash}DM-Pad64)") (class "Default")
      (node (ref "U1") (pin "64") (pinfunction "PU.1/DM_64") (pintype "bidirectional"))
    )
    (net (code "104") (name "unconnected-(U1-PUR-Pad63)") (class "Default")
      (node (ref "U1") (pin "63") (pinfunction "PUR_63") (pintype "bidirectional"))
    )
    (net (code "105") (name "unconnected-(U1-~{RST{slash}NMI{slash}SBWTDIO}-Pad76)") (class "Default")
      (node (ref "U1") (pin "76") (pinfunction "~{RST/NMI/SBWTDIO}_76") (pintype "bidirectional"))
    )
  )
)
